# sentinel_psionic_sensor.net
KiCad netlist of a schematic drawn in EAGLE
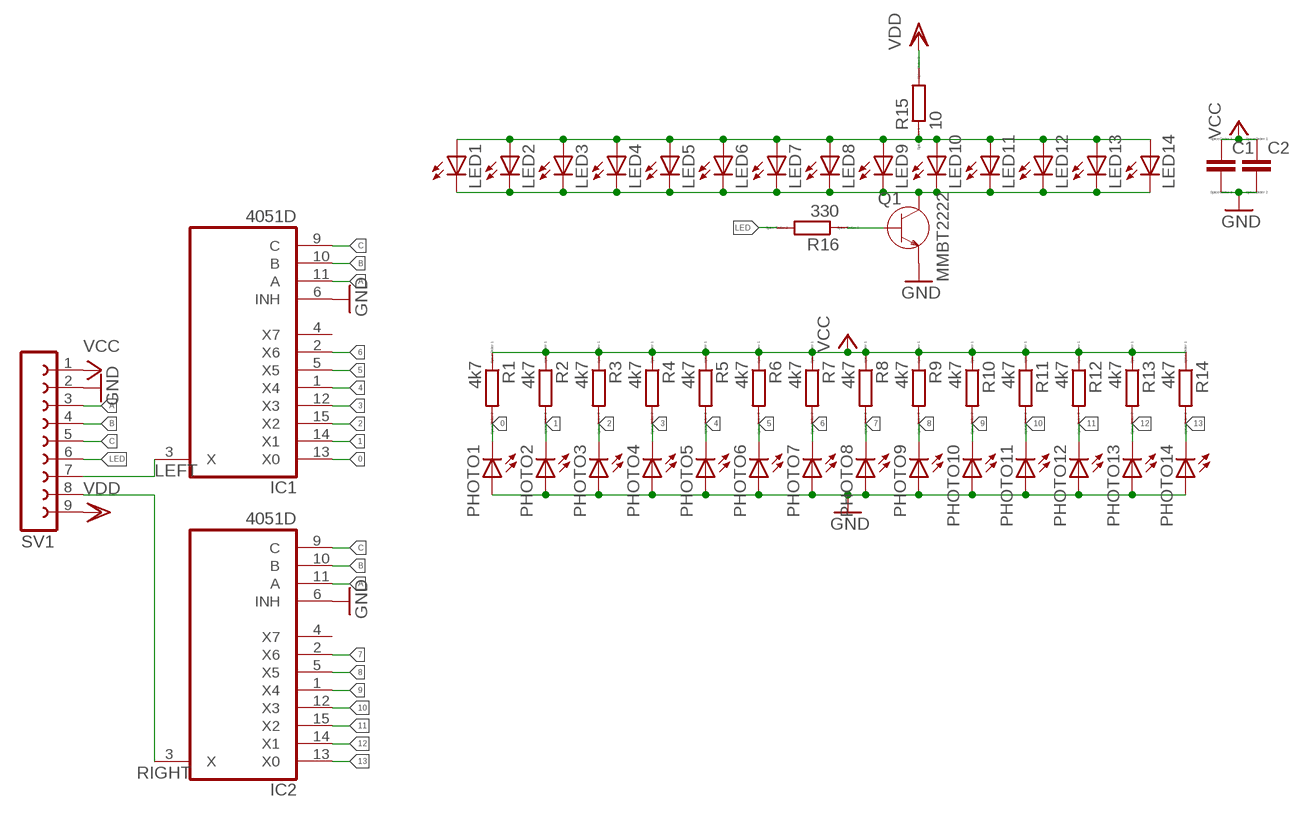
[diagram p0: schematic, sheet 1]

(export (version "E")
  (design (tool "Eeschema 10.0.6"))
  (components
    (comp (ref "C1")
      (value "CC1206")
      (footprint "eagle-import:C1206")
      (libsource (lib "eagle-import") (part "CC1206"))
    )
    (comp (ref "C2")
      (value "CC1206")
      (footprint "eagle-import:C1206")
      (libsource (lib "eagle-import") (part "CC1206"))
    )
    (comp (ref "IC1")
      (value "4051D")
      (footprint "eagle-import:SO16")
      (libsource (lib "eagle-import") (part "4051D"))
    )
    (comp (ref "IC2")
      (value "4051D")
      (footprint "eagle-import:SO16")
      (libsource (lib "eagle-import") (part "4051D"))
    )
    (comp (ref "LED1")
      (value "LED3MM")
      (footprint "eagle-import:LED3MM")
      (libsource (lib "eagle-import") (part "LED3MM"))
    )
    (comp (ref "LED2")
      (value "LED3MM")
      (footprint "eagle-import:LED3MM")
      (libsource (lib "eagle-import") (part "LED3MM"))
    )
    (comp (ref "LED3")
      (value "LED3MM")
      (footprint "eagle-import:LED3MM")
      (libsource (lib "eagle-import") (part "LED3MM"))
    )
    (comp (ref "LED4")
      (value "LED3MM")
      (footprint "eagle-import:LED3MM")
      (libsource (lib "eagle-import") (part "LED3MM"))
    )
    (comp (ref "LED5")
      (value "LED3MM")
      (footprint "eagle-import:LED3MM")
      (libsource (lib "eagle-import") (part "LED3MM"))
    )
    (comp (ref "LED6")
      (value "LED3MM")
      (footprint "eagle-import:LED3MM")
      (libsource (lib "eagle-import") (part "LED3MM"))
    )
    (comp (ref "LED7")
      (value "LED3MM")
      (footprint "eagle-import:LED3MM")
      (libsource (lib "eagle-import") (part "LED3MM"))
    )
    (comp (ref "LED8")
      (value "LED3MM")
      (footprint "eagle-import:LED3MM")
      (libsource (lib "eagle-import") (part "LED3MM"))
    )
    (comp (ref "LED9")
      (value "LED3MM")
      (footprint "eagle-import:LED3MM")
      (libsource (lib "eagle-import") (part "LED3MM"))
    )
    (comp (ref "LED10")
      (value "LED3MM")
      (footprint "eagle-import:LED3MM")
      (libsource (lib "eagle-import") (part "LED3MM"))
    )
    (comp (ref "LED11")
      (value "LED3MM")
      (footprint "eagle-import:LED3MM")
      (libsource (lib "eagle-import") (part "LED3MM"))
    )
    (comp (ref "LED12")
      (value "LED3MM")
      (footprint "eagle-import:LED3MM")
      (libsource (lib "eagle-import") (part "LED3MM"))
    )
    (comp (ref "LED13")
      (value "LED3MM")
      (footprint "eagle-import:LED3MM")
      (libsource (lib "eagle-import") (part "LED3MM"))
    )
    (comp (ref "LED14")
      (value "LED3MM")
      (footprint "eagle-import:LED3MM")
      (libsource (lib "eagle-import") (part "LED3MM"))
    )
    (comp (ref "PHOTO1")
      (value "LED3MM")
      (footprint "eagle-import:LED3MM")
      (libsource (lib "eagle-import") (part "LED3MM"))
    )
    (comp (ref "PHOTO2")
      (value "LED3MM")
      (footprint "eagle-import:LED3MM")
      (libsource (lib "eagle-import") (part "LED3MM"))
    )
    (comp (ref "PHOTO3")
      (value "LED3MM")
      (footprint "eagle-import:LED3MM")
      (libsource (lib "eagle-import") (part "LED3MM"))
    )
    (comp (ref "PHOTO4")
      (value "LED3MM")
      (footprint "eagle-import:LED3MM")
      (libsource (lib "eagle-import") (part "LED3MM"))
    )
    (comp (ref "PHOTO5")
      (value "LED3MM")
      (footprint "eagle-import:LED3MM")
      (libsource (lib "eagle-import") (part "LED3MM"))
    )
    (comp (ref "PHOTO6")
      (value "LED3MM")
      (footprint "eagle-import:LED3MM")
      (libsource (lib "eagle-import") (part "LED3MM"))
    )
    (comp (ref "PHOTO7")
      (value "LED3MM")
      (footprint "eagle-import:LED3MM")
      (libsource (lib "eagle-import") (part "LED3MM"))
    )
    (comp (ref "PHOTO8")
      (value "LED3MM")
      (footprint "eagle-import:LED3MM")
      (libsource (lib "eagle-import") (part "LED3MM"))
    )
    (comp (ref "PHOTO9")
      (value "LED3MM")
      (footprint "eagle-import:LED3MM")
      (libsource (lib "eagle-import") (part "LED3MM"))
    )
    (comp (ref "PHOTO10")
      (value "LED3MM")
      (footprint "eagle-import:LED3MM")
      (libsource (lib "eagle-import") (part "LED3MM"))
    )
    (comp (ref "PHOTO11")
      (value "LED3MM")
      (footprint "eagle-import:LED3MM")
      (libsource (lib "eagle-import") (part "LED3MM"))
    )
    (comp (ref "PHOTO12")
      (value "LED3MM")
      (footprint "eagle-import:LED3MM")
      (libsource (lib "eagle-import") (part "LED3MM"))
    )
    (comp (ref "PHOTO13")
      (value "LED3MM")
      (footprint "eagle-import:LED3MM")
      (libsource (lib "eagle-import") (part "LED3MM"))
    )
    (comp (ref "PHOTO14")
      (value "LED3MM")
      (footprint "eagle-import:LED3MM")
      (libsource (lib "eagle-import") (part "LED3MM"))
    )
    (comp (ref "Q1")
      (value "MMBT2222")
      (footprint "eagle-import:SOT23")
      (libsource (lib "eagle-import") (part "MMBT2222"))
    )
    (comp (ref "R1")
      (value "4k7")
      (footprint "eagle-import:R1206")
      (libsource (lib "eagle-import") (part "RR1206"))
    )
    (comp (ref "R2")
      (value "4k7")
      (footprint "eagle-import:R1206")
      (libsource (lib "eagle-import") (part "RR1206"))
    )
    (comp (ref "R3")
      (value "4k7")
      (footprint "eagle-import:R1206")
      (libsource (lib "eagle-import") (part "RR1206"))
    )
    (comp (ref "R4")
      (value "4k7")
      (footprint "eagle-import:R1206")
      (libsource (lib "eagle-import") (part "RR1206"))
    )
    (comp (ref "R5")
      (value "4k7")
      (footprint "eagle-import:R1206")
      (libsource (lib "eagle-import") (part "RR1206"))
    )
    (comp (ref "R6")
      (value "4k7")
      (footprint "eagle-import:R1206")
      (libsource (lib "eagle-import") (part "RR1206"))
    )
    (comp (ref "R7")
      (value "4k7")
      (footprint "eagle-import:R1206")
      (libsource (lib "eagle-import") (part "RR1206"))
    )
    (comp (ref "R8")
      (value "4k7")
      (footprint "eagle-import:R1206")
      (libsource (lib "eagle-import") (part "RR1206"))
    )
    (comp (ref "R9")
      (value "4k7")
      (footprint "eagle-import:R1206")
      (libsource (lib "eagle-import") (part "RR1206"))
    )
    (comp (ref "R10")
      (value "4k7")
      (footprint "eagle-import:R1206")
      (libsource (lib "eagle-import") (part "RR1206"))
    )
    (comp (ref "R11")
      (value "4k7")
      (footprint "eagle-import:R1206")
      (libsource (lib "eagle-import") (part "RR1206"))
    )
    (comp (ref "R12")
      (value "4k7")
      (footprint "eagle-import:R1206")
      (libsource (lib "eagle-import") (part "RR1206"))
    )
    (comp (ref "R13")
      (value "4k7")
      (footprint "eagle-import:R1206")
      (libsource (lib "eagle-import") (part "RR1206"))
    )
    (comp (ref "R14")
      (value "4k7")
      (footprint "eagle-import:R1206")
      (libsource (lib "eagle-import") (part "RR1206"))
    )
    (comp (ref "R15")
      (value "10")
      (footprint "eagle-import:R1206")
      (libsource (lib "eagle-import") (part "RR1206"))
    )
    (comp (ref "R16")
      (value "330")
      (footprint "eagle-import:R1206")
      (libsource (lib "eagle-import") (part "RR1206"))
    )
    (comp (ref "SV1")
      (value "FE09-1")
      (footprint "eagle-import:FE09")
      (libsource (lib "eagle-import") (part "FE09-1"))
    )
  )
  (nets
    (net (code "1") (name "/LEFT") (class "Default")
      (node (ref "IC1") (pin "3") (pinfunction "X_3") (pintype "bidirectional"))
      (node (ref "SV1") (pin "7") (pinfunction "7_7") (pintype "passive"))
    )
    (net (code "2") (name "/RIGHT") (class "Default")
      (node (ref "IC2") (pin "3") (pinfunction "X_3") (pintype "bidirectional"))
      (node (ref "SV1") (pin "8") (pinfunction "8_8") (pintype "passive"))
    )
    (net (code "3") (name "0") (class "Default")
      (node (ref "IC1") (pin "13") (pinfunction "X0_13") (pintype "bidirectional"))
      (node (ref "PHOTO1") (pin "K") (pinfunction "C_K") (pintype "passive"))
      (node (ref "R1") (pin "2") (pinfunction "2_2") (pintype "passive"))
    )
    (net (code "4") (name "1") (class "Default")
      (node (ref "IC1") (pin "14") (pinfunction "X1_14") (pintype "bidirectional"))
      (node (ref "PHOTO2") (pin "K") (pinfunction "C_K") (pintype "passive"))
      (node (ref "R2") (pin "2") (pinfunction "2_2") (pintype "passive"))
    )
    (net (code "5") (name "2") (class "Default")
      (node (ref "IC1") (pin "15") (pinfunction "X2_15") (pintype "bidirectional"))
      (node (ref "PHOTO3") (pin "K") (pinfunction "C_K") (pintype "passive"))
      (node (ref "R3") (pin "2") (pinfunction "2_2") (pintype "passive"))
    )
    (net (code "6") (name "3") (class "Default")
      (node (ref "IC1") (pin "12") (pinfunction "X3_12") (pintype "bidirectional"))
      (node (ref "PHOTO4") (pin "K") (pinfunction "C_K") (pintype "passive"))
      (node (ref "R4") (pin "2") (pinfunction "2_2") (pintype "passive"))
    )
    (net (code "7") (name "4") (class "Default")
      (node (ref "IC1") (pin "1") (pinfunction "X4_1") (pintype "bidirectional"))
      (node (ref "PHOTO5") (pin "K") (pinfunction "C_K") (pintype "passive"))
      (node (ref "R5") (pin "2") (pinfunction "2_2") (pintype "passive"))
    )
    (net (code "8") (name "5") (class "Default")
      (node (ref "IC1") (pin "5") (pinfunction "X5_5") (pintype "bidirectional"))
      (node (ref "PHOTO6") (pin "K") (pinfunction "C_K") (pintype "passive"))
      (node (ref "R6") (pin "2") (pinfunction "2_2") (pintype "passive"))
    )
    (net (code "9") (name "6") (class "Default")
      (node (ref "IC1") (pin "2") (pinfunction "X6_2") (pintype "bidirectional"))
      (node (ref "PHOTO7") (pin "K") (pinfunction "C_K") (pintype "passive"))
      (node (ref "R7") (pin "2") (pinfunction "2_2") (pintype "passive"))
    )
    (net (code "10") (name "7") (class "Default")
      (node (ref "IC2") (pin "2") (pinfunction "X6_2") (pintype "bidirectional"))
      (node (ref "PHOTO8") (pin "K") (pinfunction "C_K") (pintype "passive"))
      (node (ref "R8") (pin "2") (pinfunction "2_2") (pintype "passive"))
    )
    (net (code "11") (name "8") (class "Default")
      (node (ref "IC2") (pin "5") (pinfunction "X5_5") (pintype "bidirectional"))
      (node (ref "PHOTO9") (pin "K") (pinfunction "C_K") (pintype "passive"))
      (node (ref "R9") (pin "2") (pinfunction "2_2") (pintype "passive"))
    )
    (net (code "12") (name "9") (class "Default")
      (node (ref "IC2") (pin "1") (pinfunction "X4_1") (pintype "bidirectional"))
      (node (ref "PHOTO10") (pin "K") (pinfunction "C_K") (pintype "passive"))
      (node (ref "R10") (pin "2") (pinfunction "2_2") (pintype "passive"))
    )
    (net (code "13") (name "10") (class "Default")
      (node (ref "IC2") (pin "12") (pinfunction "X3_12") (pintype "bidirectional"))
      (node (ref "PHOTO11") (pin "K") (pinfunction "C_K") (pintype "passive"))
      (node (ref "R11") (pin "2") (pinfunction "2_2") (pintype "passive"))
    )
    (net (code "14") (name "11") (class "Default")
      (node (ref "IC2") (pin "15") (pinfunction "X2_15") (pintype "bidirectional"))
      (node (ref "PHOTO12") (pin "K") (pinfunction "C_K") (pintype "passive"))
      (node (ref "R12") (pin "2") (pinfunction "2_2") (pintype "passive"))
    )
    (net (code "15") (name "12") (class "Default")
      (node (ref "IC2") (pin "14") (pinfunction "X1_14") (pintype "bidirectional"))
      (node (ref "PHOTO13") (pin "K") (pinfunction "C_K") (pintype "passive"))
      (node (ref "R13") (pin "2") (pinfunction "2_2") (pintype "passive"))
    )
    (net (code "16") (name "13") (class "Default")
      (node (ref "IC2") (pin "13") (pinfunction "X0_13") (pintype "bidirectional"))
      (node (ref "PHOTO14") (pin "K") (pinfunction "C_K") (pintype "passive"))
      (node (ref "R14") (pin "2") (pinfunction "2_2") (pintype "passive"))
    )
    (net (code "17") (name "A") (class "Default")
      (node (ref "IC1") (pin "11") (pinfunction "A_11") (pintype "input"))
      (node (ref "IC2") (pin "11") (pinfunction "A_11") (pintype "input"))
      (node (ref "SV1") (pin "3") (pinfunction "3_3") (pintype "passive"))
    )
    (net (code "18") (name "B") (class "Default")
      (node (ref "IC1") (pin "10") (pinfunction "B_10") (pintype "input"))
      (node (ref "IC2") (pin "10") (pinfunction "B_10") (pintype "input"))
      (node (ref "SV1") (pin "4") (pinfunction "4_4") (pintype "passive"))
    )
    (net (code "19") (name "C") (class "Default")
      (node (ref "IC1") (pin "9") (pinfunction "C_9") (pintype "input"))
      (node (ref "IC2") (pin "9") (pinfunction "C_9") (pintype "input"))
      (node (ref "SV1") (pin "5") (pinfunction "5_5") (pintype "passive"))
    )
    (net (code "20") (name "GND") (class "Default")
      (node (ref "C1") (pin "2") (pinfunction "2_2") (pintype "passive"))
      (node (ref "C2") (pin "2") (pinfunction "2_2") (pintype "passive"))
      (node (ref "IC1") (pin "6") (pinfunction "INH_6") (pintype "input"))
      (node (ref "IC2") (pin "6") (pinfunction "INH_6") (pintype "input"))
      (node (ref "PHOTO1") (pin "A") (pinfunction "A_A") (pintype "passive"))
      (node (ref "PHOTO10") (pin "A") (pinfunction "A_A") (pintype "passive"))
      (node (ref "PHOTO11") (pin "A") (pinfunction "A_A") (pintype "passive"))
      (node (ref "PHOTO12") (pin "A") (pinfunction "A_A") (pintype "passive"))
      (node (ref "PHOTO13") (pin "A") (pinfunction "A_A") (pintype "passive"))
      (node (ref "PHOTO14") (pin "A") (pinfunction "A_A") (pintype "passive"))
      (node (ref "PHOTO2") (pin "A") (pinfunction "A_A") (pintype "passive"))
      (node (ref "PHOTO3") (pin "A") (pinfunction "A_A") (pintype "passive"))
      (node (ref "PHOTO4") (pin "A") (pinfunction "A_A") (pintype "passive"))
      (node (ref "PHOTO5") (pin "A") (pinfunction "A_A") (pintype "passive"))
      (node (ref "PHOTO6") (pin "A") (pinfunction "A_A") (pintype "passive"))
      (node (ref "PHOTO7") (pin "A") (pinfunction "A_A") (pintype "passive"))
      (node (ref "PHOTO8") (pin "A") (pinfunction "A_A") (pintype "passive"))
      (node (ref "PHOTO9") (pin "A") (pinfunction "A_A") (pintype "passive"))
      (node (ref "Q1") (pin "2") (pinfunction "E_2") (pintype "passive"))
      (node (ref "SV1") (pin "2") (pinfunction "2_2") (pintype "passive"))
    )
    (net (code "21") (name "LED") (class "Default")
      (node (ref "R16") (pin "2") (pinfunction "2_2") (pintype "passive"))
      (node (ref "SV1") (pin "6") (pinfunction "6_6") (pintype "passive"))
    )
    (net (code "22") (name "Net-(LED1-C)") (class "Default")
      (node (ref "LED1") (pin "K") (pinfunction "C_K") (pintype "passive"))
      (node (ref "LED10") (pin "K") (pinfunction "C_K") (pintype "passive"))
      (node (ref "LED11") (pin "K") (pinfunction "C_K") (pintype "passive"))
      (node (ref "LED12") (pin "K") (pinfunction "C_K") (pintype "passive"))
      (node (ref "LED13") (pin "K") (pinfunction "C_K") (pintype "passive"))
      (node (ref "LED14") (pin "K") (pinfunction "C_K") (pintype "passive"))
      (node (ref "LED2") (pin "K") (pinfunction "C_K") (pintype "passive"))
      (node (ref "LED3") (pin "K") (pinfunction "C_K") (pintype "passive"))
      (node (ref "LED4") (pin "K") (pinfunction "C_K") (pintype "passive"))
      (node (ref "LED5") (pin "K") (pinfunction "C_K") (pintype "passive"))
      (node (ref "LED6") (pin "K") (pinfunction "C_K") (pintype "passive"))
      (node (ref "LED7") (pin "K") (pinfunction "C_K") (pintype "passive"))
      (node (ref "LED8") (pin "K") (pinfunction "C_K") (pintype "passive"))
      (node (ref "LED9") (pin "K") (pinfunction "C_K") (pintype "passive"))
      (node (ref "Q1") (pin "3") (pinfunction "C_3") (pintype "passive"))
    )
    (net (code "23") (name "Net-(LED1-PadA)") (class "Default")
      (node (ref "LED1") (pin "A") (pinfunction "A_A") (pintype "passive"))
      (node (ref "LED10") (pin "A") (pinfunction "A_A") (pintype "passive"))
      (node (ref "LED11") (pin "A") (pinfunction "A_A") (pintype "passive"))
      (node (ref "LED12") (pin "A") (pinfunction "A_A") (pintype "passive"))
      (node (ref "LED13") (pin "A") (pinfunction "A_A") (pintype "passive"))
      (node (ref "LED14") (pin "A") (pinfunction "A_A") (pintype "passive"))
      (node (ref "LED2") (pin "A") (pinfunction "A_A") (pintype "passive"))
      (node (ref "LED3") (pin "A") (pinfunction "A_A") (pintype "passive"))
      (node (ref "LED4") (pin "A") (pinfunction "A_A") (pintype "passive"))
      (node (ref "LED5") (pin "A") (pinfunction "A_A") (pintype "passive"))
      (node (ref "LED6") (pin "A") (pinfunction "A_A") (pintype "passive"))
      (node (ref "LED7") (pin "A") (pinfunction "A_A") (pintype "passive"))
      (node (ref "LED8") (pin "A") (pinfunction "A_A") (pintype "passive"))
      (node (ref "LED9") (pin "A") (pinfunction "A_A") (pintype "passive"))
      (node (ref "R15") (pin "1") (pinfunction "1_1") (pintype "passive"))
    )
    (net (code "24") (name "Net-(Q1-B)") (class "Default")
      (node (ref "Q1") (pin "1") (pinfunction "B_1") (pintype "passive"))
      (node (ref "R16") (pin "1") (pinfunction "1_1") (pintype "passive"))
    )
    (net (code "25") (name "VCC") (class "Default")
      (node (ref "C1") (pin "1") (pinfunction "1_1") (pintype "passive"))
      (node (ref "C2") (pin "1") (pinfunction "1_1") (pintype "passive"))
      (node (ref "R1") (pin "1") (pinfunction "1_1") (pintype "passive"))
      (node (ref "R10") (pin "1") (pinfunction "1_1") (pintype "passive"))
      (node (ref "R11") (pin "1") (pinfunction "1_1") (pintype "passive"))
      (node (ref "R12") (pin "1") (pinfunction "1_1") (pintype "passive"))
      (node (ref "R13") (pin "1") (pinfunction "1_1") (pintype "passive"))
      (node (ref "R14") (pin "1") (pinfunction "1_1") (pintype "passive"))
      (node (ref "R2") (pin "1") (pinfunction "1_1") (pintype "passive"))
      (node (ref "R3") (pin "1") (pinfunction "1_1") (pintype "passive"))
      (node (ref "R4") (pin "1") (pinfunction "1_1") (pintype "passive"))
      (node (ref "R5") (pin "1") (pinfunction "1_1") (pintype "passive"))
      (node (ref "R6") (pin "1") (pinfunction "1_1") (pintype "passive"))
      (node (ref "R7") (pin "1") (pinfunction "1_1") (pintype "passive"))
      (node (ref "R8") (pin "1") (pinfunction "1_1") (pintype "passive"))
      (node (ref "R9") (pin "1") (pinfunction "1_1") (pintype "passive"))
      (node (ref "SV1") (pin "1") (pinfunction "1_1") (pintype "passive"))
    )
    (net (code "26") (name "VDD") (class "Default")
      (node (ref "R15") (pin "2") (pinfunction "2_2") (pintype "passive"))
      (node (ref "SV1") (pin "9") (pinfunction "9_9") (pintype "passive"))
    )
    (net (code "27") (name "unconnected-(IC1A-X7-Pad4)") (class "Default")
      (node (ref "IC1") (pin "4") (pinfunction "X7_4") (pintype "bidirectional"))
    )
    (net (code "28") (name "unconnected-(IC2A-X7-Pad4)") (class "Default")
      (node (ref "IC2") (pin "4") (pinfunction "X7_4") (pintype "bidirectional"))
    )
  )
)
